# Connectors.net
KiCad netlist of a schematic drawn in Altium Designer
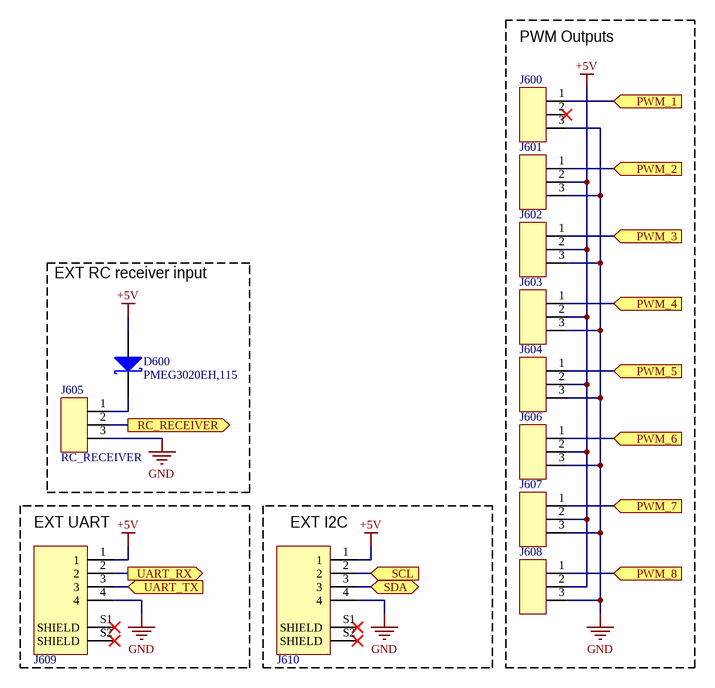
[diagram p0: Connectors.SchDoc]

(export (version "E")
  (design (tool "Eeschema 10.0.6"))
  (components
    (comp (ref "D600")
      (value "PMEG3020EH,115")
      (footprint "SOD-123")
      (description "Digikey part no. 1727-3873-1-ND")
      (libsource (lib "Moonlight-Components") (part "Schottky diode"))
    )
    (comp (ref "J600")
      (value "Generic 3 pin 100 mil header")
      (footprint "HEADER-3-POS_100_mil")
      (libsource (lib "Moonlight-Components") (part "3 pin 100 mil header"))
    )
    (comp (ref "J601")
      (value "Generic 3 pin 100 mil header")
      (footprint "HEADER-3-POS_100_mil")
      (libsource (lib "Moonlight-Components") (part "3 pin 100 mil header"))
    )
    (comp (ref "J602")
      (value "Generic 3 pin 100 mil header")
      (footprint "HEADER-3-POS_100_mil")
      (libsource (lib "Moonlight-Components") (part "3 pin 100 mil header"))
    )
    (comp (ref "J603")
      (value "Generic 3 pin 100 mil header")
      (footprint "HEADER-3-POS_100_mil")
      (libsource (lib "Moonlight-Components") (part "3 pin 100 mil header"))
    )
    (comp (ref "J604")
      (value "Generic 3 pin 100 mil header")
      (footprint "HEADER-3-POS_100_mil")
      (libsource (lib "Moonlight-Components") (part "3 pin 100 mil header"))
    )
    (comp (ref "J605")
      (value "RC_RECEIVER")
      (footprint "HEADER-3-POS_100_mil")
      (libsource (lib "Moonlight-Components") (part "3 pin 100 mil header"))
    )
    (comp (ref "J606")
      (value "Generic 3 pin 100 mil header")
      (footprint "HEADER-3-POS_100_mil")
      (libsource (lib "Moonlight-Components") (part "3 pin 100 mil header"))
    )
    (comp (ref "J607")
      (value "Generic 3 pin 100 mil header")
      (footprint "HEADER-3-POS_100_mil")
      (libsource (lib "Moonlight-Components") (part "3 pin 100 mil header"))
    )
    (comp (ref "J608")
      (value "Generic 3 pin 100 mil header")
      (footprint "HEADER-3-POS_100_mil")
      (libsource (lib "Moonlight-Components") (part "3 pin 100 mil header"))
    )
    (comp (ref "J609")
      (value "4 pin vertical JST GH")
      (footprint "JST_BM04B-GHS-TBT(LF)(SN)(N)")
      (description "JST GH vertical 4 pin\r\nDigiKey part no. 455-1580-1-ND")
      (fields (field (name "MF") "JST Sales") (field (name "DIGI-KEY_PART_NUMBER") "455-1580-1-ND"))
      (libsource (lib "Moonlight_Components") (part "BM04B-GHS-TBT(LF)(SN)(N)"))
    )
    (comp (ref "J610")
      (value "4 pin vertical JST GH")
      (footprint "JST_BM04B-GHS-TBT(LF)(SN)(N)")
      (description "JST GH vertical 4 pin\r\nDigiKey part no. 455-1580-1-ND")
      (fields (field (name "MF") "JST Sales") (field (name "DIGI-KEY_PART_NUMBER") "455-1580-1-ND"))
      (libsource (lib "Moonlight_Components") (part "BM04B-GHS-TBT(LF)(SN)(N)"))
    )
  )
  (nets
    (net (code "1") (name "+5V") (class "Default")
      (node (ref "D600") (pin "1") (pinfunction "A_1") (pintype "passive"))
      (node (ref "J601") (pin "2") (pinfunction "*_2") (pintype "passive"))
      (node (ref "J602") (pin "2") (pinfunction "*_2") (pintype "passive"))
      (node (ref "J603") (pin "2") (pinfunction "*_2") (pintype "passive"))
      (node (ref "J604") (pin "2") (pinfunction "*_2") (pintype "passive"))
      (node (ref "J606") (pin "2") (pinfunction "*_2") (pintype "passive"))
      (node (ref "J607") (pin "2") (pinfunction "*_2") (pintype "passive"))
      (node (ref "J608") (pin "2") (pinfunction "*_2") (pintype "passive"))
      (node (ref "J609") (pin "1") (pinfunction "1_1") (pintype "passive"))
      (node (ref "J610") (pin "1") (pinfunction "1_1") (pintype "passive"))
    )
    (net (code "2") (name "/PWM_1") (class "Default")
      (node (ref "J600") (pin "1") (pinfunction "*_1") (pintype "passive"))
    )
    (net (code "3") (name "/PWM_2") (class "Default")
      (node (ref "J601") (pin "1") (pinfunction "*_1") (pintype "passive"))
    )
    (net (code "4") (name "/PWM_3") (class "Default")
      (node (ref "J602") (pin "1") (pinfunction "*_1") (pintype "passive"))
    )
    (net (code "5") (name "/PWM_4") (class "Default")
      (node (ref "J603") (pin "1") (pinfunction "*_1") (pintype "passive"))
    )
    (net (code "6") (name "/PWM_5") (class "Default")
      (node (ref "J604") (pin "1") (pinfunction "*_1") (pintype "passive"))
    )
    (net (code "7") (name "/PWM_6") (class "Default")
      (node (ref "J606") (pin "1") (pinfunction "*_1") (pintype "passive"))
    )
    (net (code "8") (name "/PWM_7") (class "Default")
      (node (ref "J607") (pin "1") (pinfunction "*_1") (pintype "passive"))
    )
    (net (code "9") (name "/PWM_8") (class "Default")
      (node (ref "J608") (pin "1") (pinfunction "*_1") (pintype "passive"))
    )
    (net (code "10") (name "/RC_RECEIVER") (class "Default")
      (node (ref "J605") (pin "2") (pinfunction "*_2") (pintype "passive"))
    )
    (net (code "11") (name "/SCL") (class "Default")
      (node (ref "J610") (pin "2") (pinfunction "2_2") (pintype "passive"))
    )
    (net (code "12") (name "/SDA") (class "Default")
      (node (ref "J610") (pin "3") (pinfunction "3_3") (pintype "passive"))
    )
    (net (code "13") (name "/UART_RX") (class "Default")
      (node (ref "J609") (pin "2") (pinfunction "2_2") (pintype "passive"))
    )
    (net (code "14") (name "/UART_TX") (class "Default")
      (node (ref "J609") (pin "3") (pinfunction "3_3") (pintype "passive"))
    )
    (net (code "15") (name "GND") (class "Default")
      (node (ref "J600") (pin "3") (pinfunction "*_3") (pintype "passive"))
      (node (ref "J601") (pin "3") (pinfunction "*_3") (pintype "passive"))
      (node (ref "J602") (pin "3") (pinfunction "*_3") (pintype "passive"))
      (node (ref "J603") (pin "3") (pinfunction "*_3") (pintype "passive"))
      (node (ref "J604") (pin "3") (pinfunction "*_3") (pintype "passive"))
      (node (ref "J605") (pin "3") (pinfunction "*_3") (pintype "passive"))
      (node (ref "J606") (pin "3") (pinfunction "*_3") (pintype "passive"))
      (node (ref "J607") (pin "3") (pinfunction "*_3") (pintype "passive"))
      (node (ref "J608") (pin "3") (pinfunction "*_3") (pintype "passive"))
      (node (ref "J609") (pin "4") (pinfunction "4_4") (pintype "passive"))
      (node (ref "J610") (pin "4") (pinfunction "4_4") (pintype "passive"))
    )
    (net (code "16") (name "Net-(D600-K)") (class "Default")
      (node (ref "D600") (pin "2") (pinfunction "K_2") (pintype "passive"))
      (node (ref "J605") (pin "1") (pinfunction "*_1") (pintype "passive"))
    )
    (net (code "17") (name "unconnected-(J600-*-Pad2)") (class "Default")
      (node (ref "J600") (pin "2") (pinfunction "*_2") (pintype "passive+no_connect"))
    )
    (net (code "18") (name "unconnected-(J609-SHIELD-PadS1)") (class "Default")
      (node (ref "J609") (pin "S1") (pinfunction "SHIELD_S1") (pintype "passive+no_connect"))
    )
    (net (code "19") (name "unconnected-(J609-SHIELD-PadS2)") (class "Default")
      (node (ref "J609") (pin "S2") (pinfunction "SHIELD_S2") (pintype "passive+no_connect"))
    )
    (net (code "20") (name "unconnected-(J610-SHIELD-PadS1)") (class "Default")
      (node (ref "J610") (pin "S1") (pinfunction "SHIELD_S1") (pintype "passive+no_connect"))
    )
    (net (code "21") (name "unconnected-(J610-SHIELD-PadS2)") (class "Default")
      (node (ref "J610") (pin "S2") (pinfunction "SHIELD_S2") (pintype "passive+no_connect"))
    )
  )
)
